# OLED.net
KiCad netlist of a schematic drawn in Altium Designer
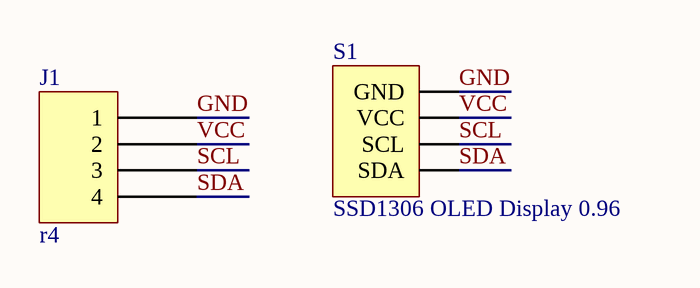
[diagram p0: OLED.SchDoc]

(export (version "E")
  (design (tool "Eeschema 10.0.6"))
  (components
    (comp (ref "J1")
      (value "r4")
      (footprint "MOLEX SDA-70553-4PIN")
      (libsource (lib "Connectors") (part "r4"))
    )
    (comp (ref "S1")
      (value "SSD1306 OLED Display 0.96")
      (footprint "OLED")
      (libsource (lib "Sensors") (part "OLED"))
    )
  )
  (nets
    (net (code "1") (name "/GND") (class "Default")
      (node (ref "J1") (pin "1") (pinfunction "1_1") (pintype "passive"))
      (node (ref "S1") (pin "1") (pinfunction "GND_1") (pintype "passive"))
    )
    (net (code "2") (name "/SCL") (class "Default")
      (node (ref "J1") (pin "3") (pinfunction "3_3") (pintype "passive"))
      (node (ref "S1") (pin "3") (pinfunction "SCL_3") (pintype "passive"))
    )
    (net (code "3") (name "/SDA") (class "Default")
      (node (ref "J1") (pin "4") (pinfunction "4_4") (pintype "passive"))
      (node (ref "S1") (pin "4") (pinfunction "SDA_4") (pintype "passive"))
    )
    (net (code "4") (name "/VCC") (class "Default")
      (node (ref "J1") (pin "2") (pinfunction "2_2") (pintype "passive"))
      (node (ref "S1") (pin "2") (pinfunction "VCC_2") (pintype "passive"))
    )
  )
)
